# FMC_connector.net
KiCad netlist of a schematic drawn in Altium Designer
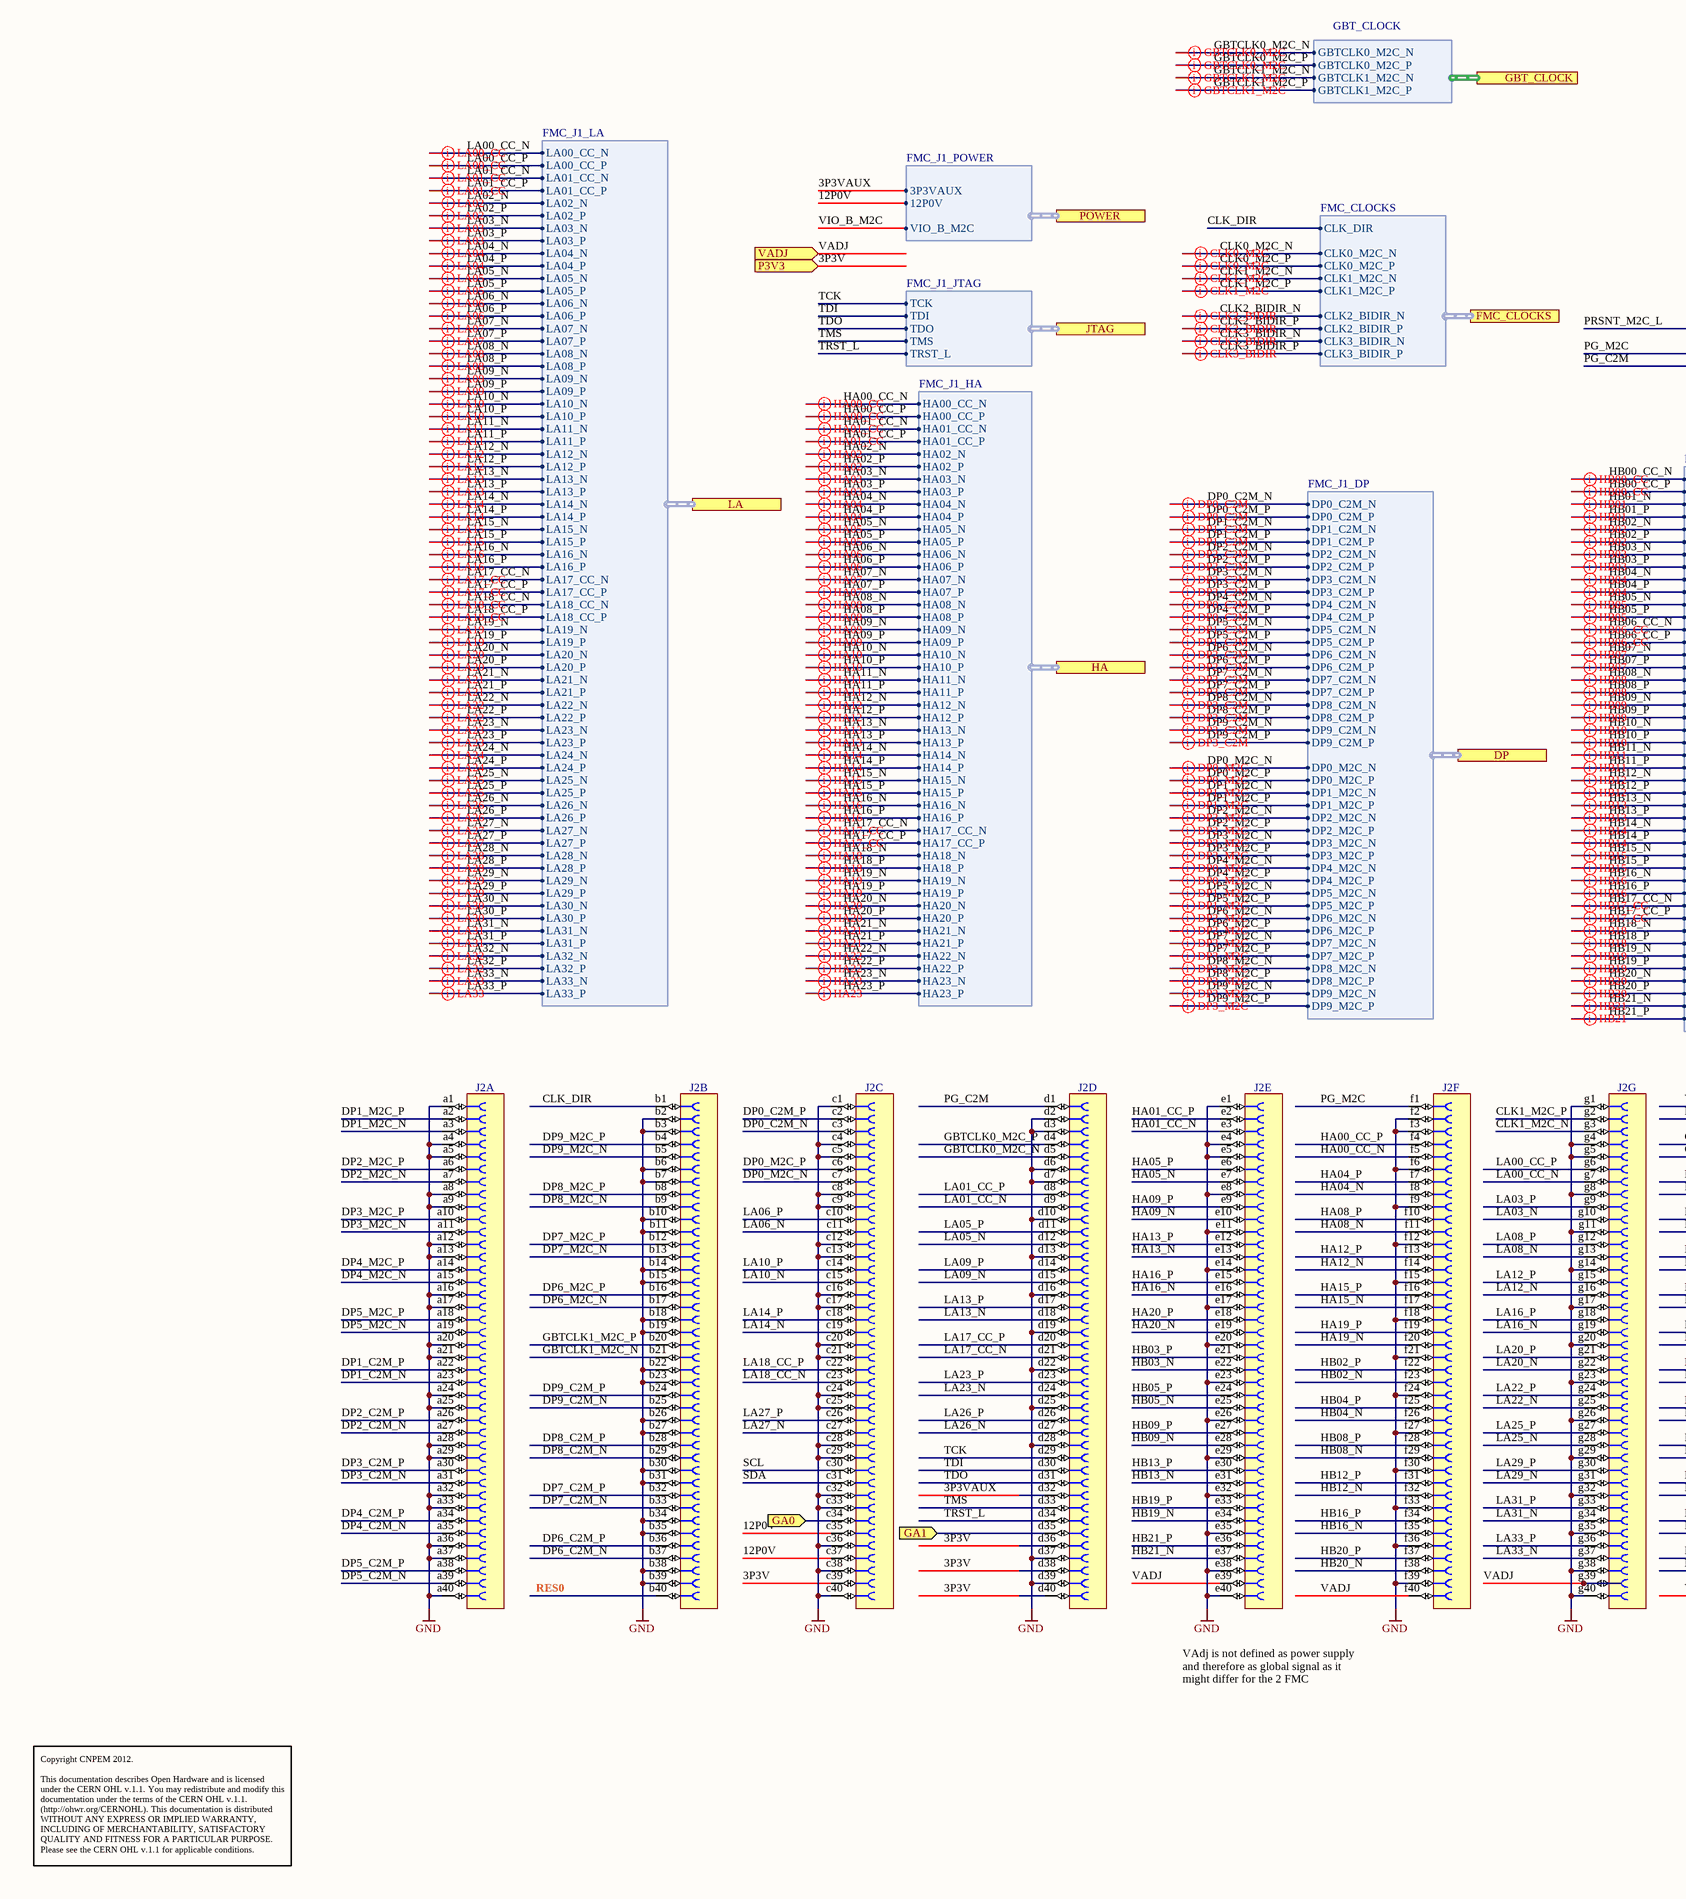
[diagram p0: FMC_connector.SchDoc, left]
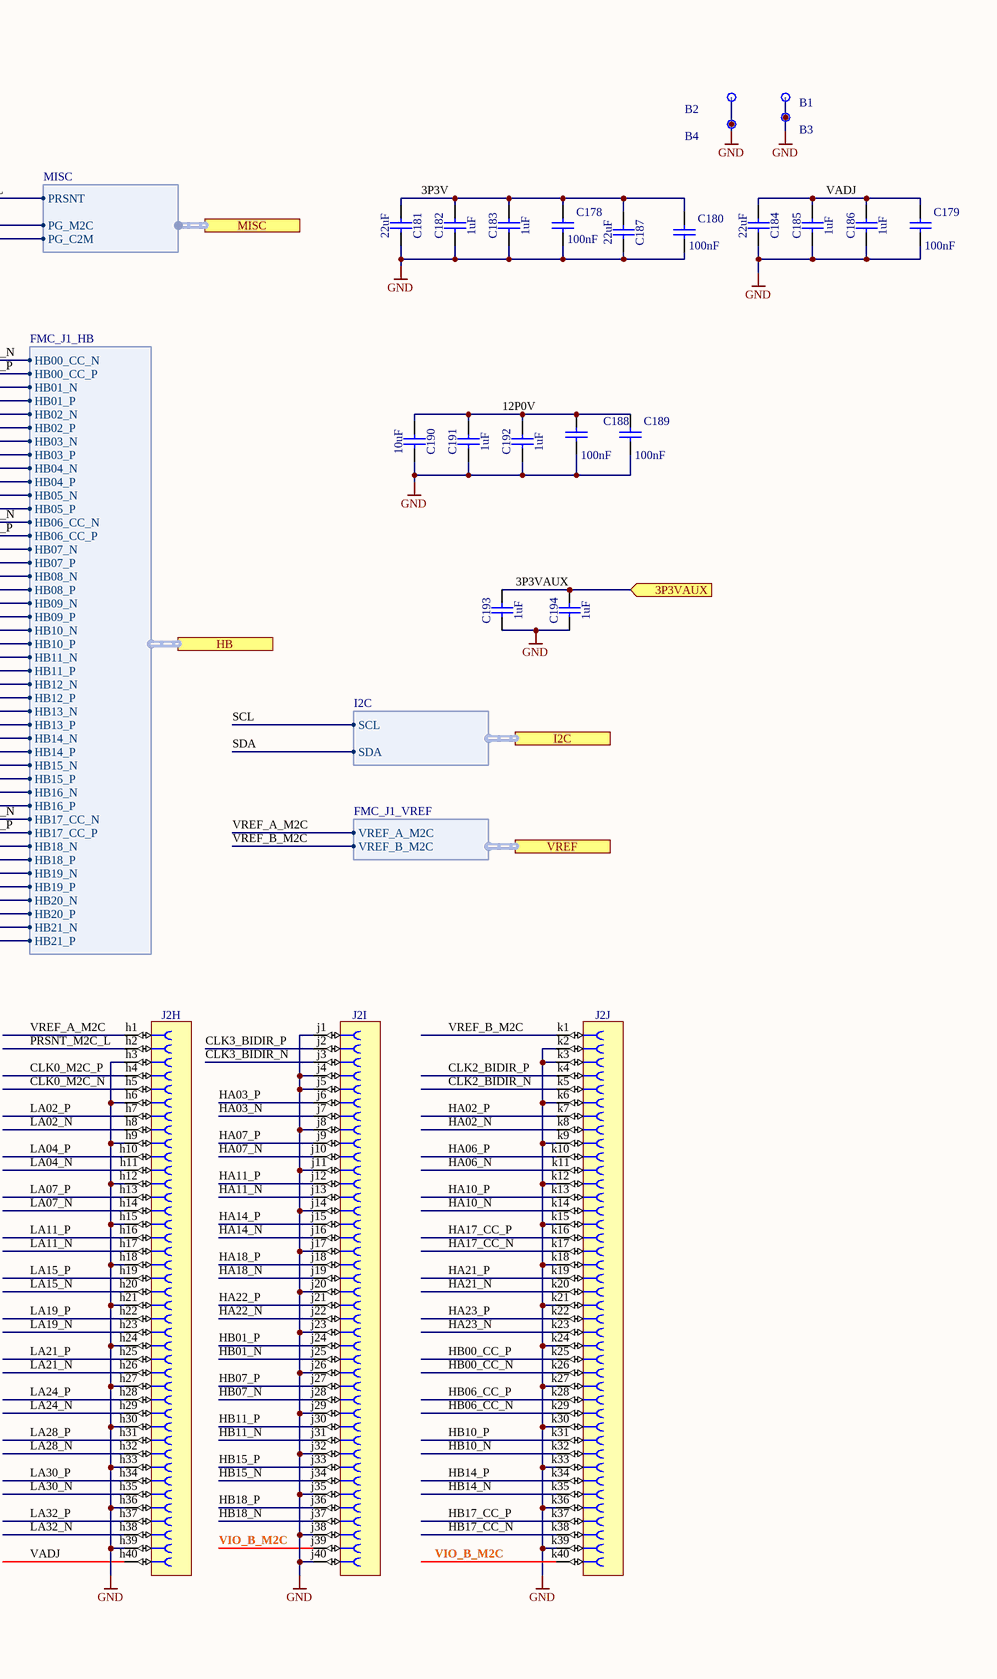
[diagram p1: FMC_connector.SchDoc, right]

(export (version "E")
  (design (tool "Eeschema 10.0.6"))
  (components
    (comp (ref "B1")
      (value "Plated Hole")
      (footprint "MTG270_500")
      (description "Single Terminal Socket")
      (fields (field (name "PART NUMBER") "PLATED_HOLE2.7_PAD5.0") (field (name "AUTHOR") "CERN DEM JMW"))
      (libsource (lib "Eletro-mechanical") (part "Single Terminal Socket"))
    )
    (comp (ref "B2")
      (value "Plated Hole")
      (footprint "MTG270_500")
      (description "Single Terminal Socket")
      (fields (field (name "PART NUMBER") "PLATED_HOLE2.7_PAD5.0") (field (name "AUTHOR") "CERN DEM JMW"))
      (libsource (lib "Eletro-mechanical") (part "Single Terminal Socket"))
    )
    (comp (ref "B3")
      (value "Plated Hole")
      (footprint "MTG270_500")
      (description "Single Terminal Socket")
      (fields (field (name "PART NUMBER") "PLATED_HOLE2.7_PAD5.0") (field (name "AUTHOR") "CERN DEM JMW"))
      (libsource (lib "Eletro-mechanical") (part "Single Terminal Socket"))
    )
    (comp (ref "B4")
      (value "Plated Hole")
      (footprint "MTG270_500")
      (description "Single Terminal Socket")
      (fields (field (name "PART NUMBER") "PLATED_HOLE2.7_PAD5.0") (field (name "AUTHOR") "CERN DEM JMW"))
      (libsource (lib "Eletro-mechanical") (part "Single Terminal Socket"))
    )
    (comp (ref "C178")
      (value "100nF")
      (footprint "CAPC0603X33N")
      (description "Non-polarised capacitor")
      (fields
        (field (name "PART NUMBER") "CC0201_100NF_6.3V_10%_X5R")
        (field (name "VOLTAGE") "6.3V")
        (field (name "AUTHOR") "CERN DEM JLC")
      )
      (libsource (lib "Capacitors") (part "Capacitor - non polarized"))
    )
    (comp (ref "C179")
      (value "100nF")
      (footprint "CAPC0603X33N")
      (description "Non-polarised capacitor")
      (fields
        (field (name "PART NUMBER") "CC0201_100NF_6.3V_10%_X5R")
        (field (name "VOLTAGE") "6.3V")
        (field (name "AUTHOR") "CERN DEM JLC")
      )
      (libsource (lib "Capacitors") (part "Capacitor - non polarized"))
    )
    (comp (ref "C180")
      (value "100nF")
      (footprint "CAPC0603X33N")
      (description "Non-polarised capacitor")
      (fields
        (field (name "PART NUMBER") "CC0201_100NF_6.3V_10%_X5R")
        (field (name "VOLTAGE") "6.3V")
        (field (name "AUTHOR") "CERN DEM JLC")
      )
      (libsource (lib "Capacitors") (part "Capacitor - non polarized"))
    )
    (comp (ref "C181")
      (value "22uF")
      (footprint "CAPC3216X180N")
      (description "Non-polarised capacitor")
      (fields
        (field (name "PART NUMBER") "CC1206_22UF_10V_10%_X7R")
        (field (name "VOLTAGE") "10V")
        (field (name "AUTHOR") "CERN DEM JLC")
      )
      (libsource (lib "Capacitors") (part "Capacitor - non polarized"))
    )
    (comp (ref "C182")
      (value "1uF")
      (footprint "CAPC1608X87N")
      (description "Non-polarised capacitor")
      (fields
        (field (name "PART NUMBER") "CC0603_1UF_25V_10%_X7R")
        (field (name "VOLTAGE") "25V")
        (field (name "AUTHOR") "CERN DEM JLC")
      )
      (libsource (lib "Capacitors") (part "Capacitor - non polarized"))
    )
    (comp (ref "C183")
      (value "1uF")
      (footprint "CAPC1608X87N")
      (description "Non-polarised capacitor")
      (fields
        (field (name "PART NUMBER") "CC0603_1UF_25V_10%_X7R")
        (field (name "VOLTAGE") "25V")
        (field (name "AUTHOR") "CERN DEM JLC")
      )
      (libsource (lib "Capacitors") (part "Capacitor - non polarized"))
    )
    (comp (ref "C184")
      (value "22uF")
      (footprint "CAPC3216X180N")
      (description "Non-polarised capacitor")
      (fields
        (field (name "PART NUMBER") "CC1206_22UF_10V_10%_X7R")
        (field (name "VOLTAGE") "10V")
        (field (name "AUTHOR") "CERN DEM JLC")
      )
      (libsource (lib "Capacitors") (part "Capacitor - non polarized"))
    )
    (comp (ref "C185")
      (value "1uF")
      (footprint "CAPC1608X87N")
      (description "Non-polarised capacitor")
      (fields
        (field (name "PART NUMBER") "CC0603_1UF_25V_10%_X7R")
        (field (name "VOLTAGE") "25V")
        (field (name "AUTHOR") "CERN DEM JLC")
      )
      (libsource (lib "Capacitors") (part "Capacitor - non polarized"))
    )
    (comp (ref "C186")
      (value "1uF")
      (footprint "CAPC1608X87N")
      (description "Non-polarised capacitor")
      (fields
        (field (name "PART NUMBER") "CC0603_1UF_25V_10%_X7R")
        (field (name "VOLTAGE") "25V")
        (field (name "AUTHOR") "CERN DEM JLC")
      )
      (libsource (lib "Capacitors") (part "Capacitor - non polarized"))
    )
    (comp (ref "C187")
      (value "22uF")
      (footprint "CAPC3216X180N")
      (description "Non-polarised capacitor")
      (fields
        (field (name "PART NUMBER") "CC1206_22UF_10V_10%_X7R")
        (field (name "VOLTAGE") "10V")
        (field (name "AUTHOR") "CERN DEM JLC")
      )
      (libsource (lib "Capacitors") (part "Capacitor - non polarized"))
    )
    (comp (ref "C188")
      (value "100nF")
      (footprint "CAPC0603X33N")
      (description "Non-polarised capacitor")
      (fields
        (field (name "PART NUMBER") "CC0201_100NF_6.3V_10%_X5R")
        (field (name "VOLTAGE") "6.3V")
        (field (name "AUTHOR") "CERN DEM JLC")
      )
      (libsource (lib "Capacitors") (part "Capacitor - non polarized"))
    )
    (comp (ref "C189")
      (value "100nF")
      (footprint "CAPC0603X33N")
      (description "Non-polarised capacitor")
      (fields
        (field (name "PART NUMBER") "CC0201_100NF_6.3V_10%_X5R")
        (field (name "VOLTAGE") "6.3V")
        (field (name "AUTHOR") "CERN DEM JLC")
      )
      (libsource (lib "Capacitors") (part "Capacitor - non polarized"))
    )
    (comp (ref "C190")
      (value "10uF")
      (footprint "CAPC2012X135N")
      (description "Non-polarised capacitor")
      (fields
        (field (name "PART NUMBER") "CC0805_10UF_16V_10%_X5R")
        (field (name "VOLTAGE") "16V")
        (field (name "AUTHOR") "CERN DEM JLC")
      )
      (libsource (lib "Capacitors") (part "Capacitor - non polarized"))
    )
    (comp (ref "C191")
      (value "1uF")
      (footprint "CAPC1608X87N")
      (description "Non-polarised capacitor")
      (fields
        (field (name "PART NUMBER") "CC0603_1UF_25V_10%_X7R")
        (field (name "VOLTAGE") "25V")
        (field (name "AUTHOR") "CERN DEM JLC")
      )
      (libsource (lib "Capacitors") (part "Capacitor - non polarized"))
    )
    (comp (ref "C192")
      (value "1uF")
      (footprint "CAPC1608X87N")
      (description "Non-polarised capacitor")
      (fields
        (field (name "PART NUMBER") "CC0603_1UF_25V_10%_X7R")
        (field (name "VOLTAGE") "25V")
        (field (name "AUTHOR") "CERN DEM JLC")
      )
      (libsource (lib "Capacitors") (part "Capacitor - non polarized"))
    )
    (comp (ref "C193")
      (value "1uF")
      (footprint "CAPC1608X87N")
      (description "Non-polarised capacitor")
      (fields
        (field (name "PART NUMBER") "CC0603_1UF_25V_10%_X7R")
        (field (name "VOLTAGE") "25V")
        (field (name "AUTHOR") "CERN DEM JLC")
      )
      (libsource (lib "Capacitors") (part "Capacitor - non polarized"))
    )
    (comp (ref "C194")
      (value "1uF")
      (footprint "CAPC1608X87N")
      (description "Non-polarised capacitor")
      (fields
        (field (name "PART NUMBER") "CC0603_1UF_25V_10%_X7R")
        (field (name "VOLTAGE") "25V")
        (field (name "AUTHOR") "CERN DEM JLC")
      )
      (libsource (lib "Capacitors") (part "Capacitor - non polarized"))
    )
    (comp (ref "J2")
      (value "VITA 57")
      (footprint "SAMTEC_ASP-134486-01")
      (description "Connector VITA 57, 400 Female contacts in 10 row abcdefghj")
      (fields
        (field (name "PART NUMBER") "SAMTEC_ASP-134486-01")
        (field (name "MANUFACTURER") "SAMTEC")
        (field (name "AUTHOR") "CERN DEM JLC")
      )
      (libsource (lib "Connectors") (part "Connector VITA 57 400 Female (abcdefghjk)"))
    )
  )
  (nets
    (net (code "12") (name "/3P3V") (class "Default")
      (node (ref "C178") (pin "2") (pinfunction "2_2") (pintype "passive"))
      (node (ref "C180") (pin "2") (pinfunction "2_2") (pintype "passive"))
      (node (ref "C181") (pin "1") (pinfunction "1_1") (pintype "passive"))
      (node (ref "C182") (pin "2") (pinfunction "2_2") (pintype "passive"))
      (node (ref "C183") (pin "2") (pinfunction "2_2") (pintype "passive"))
      (node (ref "C187") (pin "1") (pinfunction "1_1") (pintype "passive"))
      (node (ref "J2") (pin "c39") (pinfunction "c39_c39") (pintype "bidirectional"))
      (node (ref "J2") (pin "d36") (pinfunction "d36_d36") (pintype "bidirectional"))
      (node (ref "J2") (pin "d38") (pinfunction "d38_d38") (pintype "bidirectional"))
      (node (ref "J2") (pin "d40") (pinfunction "d40_d40") (pintype "bidirectional"))
    )
    (net (code "13") (name "/3P3VAUX") (class "Default")
      (node (ref "C193") (pin "2") (pinfunction "2_2") (pintype "passive"))
      (node (ref "C194") (pin "2") (pinfunction "2_2") (pintype "passive"))
      (node (ref "J2") (pin "d32") (pinfunction "d32_d32") (pintype "bidirectional"))
    )
    (net (code "14") (name "/12P0V") (class "Default")
      (node (ref "C188") (pin "2") (pinfunction "2_2") (pintype "passive"))
      (node (ref "C189") (pin "2") (pinfunction "2_2") (pintype "passive"))
      (node (ref "C190") (pin "1") (pinfunction "1_1") (pintype "passive"))
      (node (ref "C191") (pin "2") (pinfunction "2_2") (pintype "passive"))
      (node (ref "C192") (pin "2") (pinfunction "2_2") (pintype "passive"))
      (node (ref "J2") (pin "c35") (pinfunction "c35_c35") (pintype "bidirectional"))
      (node (ref "J2") (pin "c37") (pinfunction "c37_c37") (pintype "bidirectional"))
    )
    (net (code "15") (name "/CLK0_M2C_N") (class "Default")
      (node (ref "J2") (pin "h5") (pinfunction "h5_h5") (pintype "bidirectional"))
    )
    (net (code "16") (name "/CLK0_M2C_P") (class "Default")
      (node (ref "J2") (pin "h4") (pinfunction "h4_h4") (pintype "bidirectional"))
    )
    (net (code "17") (name "/CLK1_M2C_N") (class "Default")
      (node (ref "J2") (pin "g3") (pinfunction "g3_g3") (pintype "bidirectional"))
    )
    (net (code "18") (name "/CLK1_M2C_P") (class "Default")
      (node (ref "J2") (pin "g2") (pinfunction "g2_g2") (pintype "bidirectional"))
    )
    (net (code "19") (name "/CLK2_BIDIR_N") (class "Default")
      (node (ref "J2") (pin "k5") (pinfunction "k5_k5") (pintype "bidirectional"))
    )
    (net (code "20") (name "/CLK2_BIDIR_P") (class "Default")
      (node (ref "J2") (pin "k4") (pinfunction "k4_k4") (pintype "bidirectional"))
    )
    (net (code "21") (name "/CLK3_BIDIR_N") (class "Default")
      (node (ref "J2") (pin "j3") (pinfunction "j3_j3") (pintype "bidirectional"))
    )
    (net (code "22") (name "/CLK3_BIDIR_P") (class "Default")
      (node (ref "J2") (pin "j2") (pinfunction "j2_j2") (pintype "bidirectional"))
    )
    (net (code "23") (name "/CLK_DIR") (class "Default")
      (node (ref "J2") (pin "b1") (pinfunction "b1_b1") (pintype "bidirectional"))
    )
    (net (code "24") (name "/DP0_C2M_N") (class "Default")
      (node (ref "J2") (pin "c3") (pinfunction "c3_c3") (pintype "bidirectional"))
    )
    (net (code "25") (name "/DP0_C2M_P") (class "Default")
      (node (ref "J2") (pin "c2") (pinfunction "c2_c2") (pintype "bidirectional"))
    )
    (net (code "26") (name "/DP0_M2C_N") (class "Default")
      (node (ref "J2") (pin "c7") (pinfunction "c7_c7") (pintype "bidirectional"))
    )
    (net (code "27") (name "/DP0_M2C_P") (class "Default")
      (node (ref "J2") (pin "c6") (pinfunction "c6_c6") (pintype "bidirectional"))
    )
    (net (code "28") (name "/DP1_C2M_N") (class "Default")
      (node (ref "J2") (pin "a23") (pinfunction "a23_a23") (pintype "bidirectional"))
    )
    (net (code "29") (name "/DP1_C2M_P") (class "Default")
      (node (ref "J2") (pin "a22") (pinfunction "a22_a22") (pintype "bidirectional"))
    )
    (net (code "30") (name "/DP1_M2C_N") (class "Default")
      (node (ref "J2") (pin "a3") (pinfunction "a3_a3") (pintype "bidirectional"))
    )
    (net (code "31") (name "/DP1_M2C_P") (class "Default")
      (node (ref "J2") (pin "a2") (pinfunction "a2_a2") (pintype "bidirectional"))
    )
    (net (code "32") (name "/DP2_C2M_N") (class "Default")
      (node (ref "J2") (pin "a27") (pinfunction "a27_a27") (pintype "bidirectional"))
    )
    (net (code "33") (name "/DP2_C2M_P") (class "Default")
      (node (ref "J2") (pin "a26") (pinfunction "a26_a26") (pintype "bidirectional"))
    )
    (net (code "34") (name "/DP2_M2C_N") (class "Default")
      (node (ref "J2") (pin "a7") (pinfunction "a7_a7") (pintype "bidirectional"))
    )
    (net (code "35") (name "/DP2_M2C_P") (class "Default")
      (node (ref "J2") (pin "a6") (pinfunction "a6_a6") (pintype "bidirectional"))
    )
    (net (code "36") (name "/DP3_C2M_N") (class "Default")
      (node (ref "J2") (pin "a31") (pinfunction "a31_a31") (pintype "bidirectional"))
    )
    (net (code "37") (name "/DP3_C2M_P") (class "Default")
      (node (ref "J2") (pin "a30") (pinfunction "a30_a30") (pintype "bidirectional"))
    )
    (net (code "38") (name "/DP3_M2C_N") (class "Default")
      (node (ref "J2") (pin "a11") (pinfunction "a11_a11") (pintype "bidirectional"))
    )
    (net (code "39") (name "/DP3_M2C_P") (class "Default")
      (node (ref "J2") (pin "a10") (pinfunction "a10_a10") (pintype "bidirectional"))
    )
    (net (code "40") (name "/DP4_C2M_N") (class "Default")
      (node (ref "J2") (pin "a35") (pinfunction "a35_a35") (pintype "bidirectional"))
    )
    (net (code "41") (name "/DP4_C2M_P") (class "Default")
      (node (ref "J2") (pin "a34") (pinfunction "a34_a34") (pintype "bidirectional"))
    )
    (net (code "42") (name "/DP4_M2C_N") (class "Default")
      (node (ref "J2") (pin "a15") (pinfunction "a15_a15") (pintype "bidirectional"))
    )
    (net (code "43") (name "/DP4_M2C_P") (class "Default")
      (node (ref "J2") (pin "a14") (pinfunction "a14_a14") (pintype "bidirectional"))
    )
    (net (code "44") (name "/DP5_C2M_N") (class "Default")
      (node (ref "J2") (pin "a39") (pinfunction "a39_a39") (pintype "bidirectional"))
    )
    (net (code "45") (name "/DP5_C2M_P") (class "Default")
      (node (ref "J2") (pin "a38") (pinfunction "a38_a38") (pintype "bidirectional"))
    )
    (net (code "46") (name "/DP5_M2C_N") (class "Default")
      (node (ref "J2") (pin "a19") (pinfunction "a19_a19") (pintype "bidirectional"))
    )
    (net (code "47") (name "/DP5_M2C_P") (class "Default")
      (node (ref "J2") (pin "a18") (pinfunction "a18_a18") (pintype "bidirectional"))
    )
    (net (code "48") (name "/DP6_C2M_N") (class "Default")
      (node (ref "J2") (pin "b37") (pinfunction "b37_b37") (pintype "bidirectional"))
    )
    (net (code "49") (name "/DP6_C2M_P") (class "Default")
      (node (ref "J2") (pin "b36") (pinfunction "b36_b36") (pintype "bidirectional"))
    )
    (net (code "50") (name "/DP6_M2C_N") (class "Default")
      (node (ref "J2") (pin "b17") (pinfunction "b17_b17") (pintype "bidirectional"))
    )
    (net (code "51") (name "/DP6_M2C_P") (class "Default")
      (node (ref "J2") (pin "b16") (pinfunction "b16_b16") (pintype "bidirectional"))
    )
    (net (code "52") (name "/DP7_C2M_N") (class "Default")
      (node (ref "J2") (pin "b33") (pinfunction "b33_b33") (pintype "bidirectional"))
    )
    (net (code "53") (name "/DP7_C2M_P") (class "Default")
      (node (ref "J2") (pin "b32") (pinfunction "b32_b32") (pintype "bidirectional"))
    )
    (net (code "54") (name "/DP7_M2C_N") (class "Default")
      (node (ref "J2") (pin "b13") (pinfunction "b13_b13") (pintype "bidirectional"))
    )
    (net (code "55") (name "/DP7_M2C_P") (class "Default")
      (node (ref "J2") (pin "b12") (pinfunction "b12_b12") (pintype "bidirectional"))
    )
    (net (code "56") (name "/DP8_C2M_N") (class "Default")
      (node (ref "J2") (pin "b29") (pinfunction "b29_b29") (pintype "bidirectional"))
    )
    (net (code "57") (name "/DP8_C2M_P") (class "Default")
      (node (ref "J2") (pin "b28") (pinfunction "b28_b28") (pintype "bidirectional"))
    )
    (net (code "58") (name "/DP8_M2C_N") (class "Default")
      (node (ref "J2") (pin "b9") (pinfunction "b9_b9") (pintype "bidirectional"))
    )
    (net (code "59") (name "/DP8_M2C_P") (class "Default")
      (node (ref "J2") (pin "b8") (pinfunction "b8_b8") (pintype "bidirectional"))
    )
    (net (code "60") (name "/DP9_C2M_N") (class "Default")
      (node (ref "J2") (pin "b25") (pinfunction "b25_b25") (pintype "bidirectional"))
    )
    (net (code "61") (name "/DP9_C2M_P") (class "Default")
      (node (ref "J2") (pin "b24") (pinfunction "b24_b24") (pintype "bidirectional"))
    )
    (net (code "62") (name "/DP9_M2C_N") (class "Default")
      (node (ref "J2") (pin "b5") (pinfunction "b5_b5") (pintype "bidirectional"))
    )
    (net (code "63") (name "/DP9_M2C_P") (class "Default")
      (node (ref "J2") (pin "b4") (pinfunction "b4_b4") (pintype "bidirectional"))
    )
    (net (code "64") (name "/GA0") (class "Default")
      (node (ref "J2") (pin "c34") (pinfunction "c34_c34") (pintype "bidirectional"))
    )
    (net (code "65") (name "/GA1") (class "Default")
      (node (ref "J2") (pin "d35") (pinfunction "d35_d35") (pintype "bidirectional"))
    )
    (net (code "66") (name "/GBTCLK0_M2C_N") (class "Default")
      (node (ref "J2") (pin "d5") (pinfunction "d5_d5") (pintype "bidirectional"))
    )
    (net (code "67") (name "/GBTCLK0_M2C_P") (class "Default")
      (node (ref "J2") (pin "d4") (pinfunction "d4_d4") (pintype "bidirectional"))
    )
    (net (code "68") (name "/GBTCLK1_M2C_N") (class "Default")
      (node (ref "J2") (pin "b21") (pinfunction "b21_b21") (pintype "bidirectional"))
    )
    (net (code "69") (name "/GBTCLK1_M2C_P") (class "Default")
      (node (ref "J2") (pin "b20") (pinfunction "b20_b20") (pintype "bidirectional"))
    )
    (net (code "70") (name "/HA00_CC_N") (class "Default")
      (node (ref "J2") (pin "f5") (pinfunction "f5_f5") (pintype "bidirectional"))
    )
    (net (code "71") (name "/HA00_CC_P") (class "Default")
      (node (ref "J2") (pin "f4") (pinfunction "f4_f4") (pintype "bidirectional"))
    )
    (net (code "72") (name "/HA01_CC_N") (class "Default")
      (node (ref "J2") (pin "e3") (pinfunction "e3_e3") (pintype "bidirectional"))
    )
    (net (code "73") (name "/HA01_CC_P") (class "Default")
      (node (ref "J2") (pin "e2") (pinfunction "e2_e2") (pintype "bidirectional"))
    )
    (net (code "74") (name "/HA02_N") (class "Default")
      (node (ref "J2") (pin "k8") (pinfunction "k8_k8") (pintype "bidirectional"))
    )
    (net (code "75") (name "/HA02_P") (class "Default")
      (node (ref "J2") (pin "k7") (pinfunction "k7_k7") (pintype "bidirectional"))
    )
    (net (code "76") (name "/HA03_N") (class "Default")
      (node (ref "J2") (pin "j7") (pinfunction "j7_j7") (pintype "bidirectional"))
    )
    (net (code "77") (name "/HA03_P") (class "Default")
      (node (ref "J2") (pin "j6") (pinfunction "j6_j6") (pintype "bidirectional"))
    )
    (net (code "78") (name "/HA04_N") (class "Default")
      (node (ref "J2") (pin "f8") (pinfunction "f8_f8") (pintype "bidirectional"))
    )
    (net (code "79") (name "/HA04_P") (class "Default")
      (node (ref "J2") (pin "f7") (pinfunction "f7_f7") (pintype "bidirectional"))
    )
    (net (code "80") (name "/HA05_N") (class "Default")
      (node (ref "J2") (pin "e7") (pinfunction "e7_e7") (pintype "bidirectional"))
    )
    (net (code "81") (name "/HA05_P") (class "Default")
      (node (ref "J2") (pin "e6") (pinfunction "e6_e6") (pintype "bidirectional"))
    )
    (net (code "82") (name "/HA06_N") (class "Default")
      (node (ref "J2") (pin "k11") (pinfunction "k11_k11") (pintype "bidirectional"))
    )
    (net (code "83") (name "/HA06_P") (class "Default")
      (node (ref "J2") (pin "k10") (pinfunction "k10_k10") (pintype "bidirectional"))
    )
    (net (code "84") (name "/HA07_N") (class "Default")
      (node (ref "J2") (pin "j10") (pinfunction "j10_j10") (pintype "bidirectional"))
    )
    (net (code "85") (name "/HA07_P") (class "Default")
      (node (ref "J2") (pin "j9") (pinfunction "j9_j9") (pintype "bidirectional"))
    )
    (net (code "86") (name "/HA08_N") (class "Default")
      (node (ref "J2") (pin "f11") (pinfunction "f11_f11") (pintype "bidirectional"))
    )
    (net (code "87") (name "/HA08_P") (class "Default")
      (node (ref "J2") (pin "f10") (pinfunction "f10_f10") (pintype "bidirectional"))
    )
    (net (code "88") (name "/HA09_N") (class "Default")
      (node (ref "J2") (pin "e10") (pinfunction "e10_e10") (pintype "bidirectional"))
    )
    (net (code "89") (name "/HA09_P") (class "Default")
      (node (ref "J2") (pin "e9") (pinfunction "e9_e9") (pintype "bidirectional"))
    )
    (net (code "90") (name "/HA10_N") (class "Default")
      (node (ref "J2") (pin "k14") (pinfunction "k14_k14") (pintype "bidirectional"))
    )
    (net (code "91") (name "/HA10_P") (class "Default")
      (node (ref "J2") (pin "k13") (pinfunction "k13_k13") (pintype "bidirectional"))
    )
    (net (code "92") (name "/HA11_N") (class "Default")
      (node (ref "J2") (pin "j13") (pinfunction "j13_j13") (pintype "bidirectional"))
    )
    (net (code "93") (name "/HA11_P") (class "Default")
      (node (ref "J2") (pin "j12") (pinfunction "j12_j12") (pintype "bidirectional"))
    )
    (net (code "94") (name "/HA12_N") (class "Default")
      (node (ref "J2") (pin "f14") (pinfunction "f14_f14") (pintype "bidirectional"))
    )
    (net (code "95") (name "/HA12_P") (class "Default")
      (node (ref "J2") (pin "f13") (pinfunction "f13_f13") (pintype "bidirectional"))
    )
    (net (code "96") (name "/HA13_N") (class "Default")
      (node (ref "J2") (pin "e13") (pinfunction "e13_e13") (pintype "bidirectional"))
    )
    (net (code "97") (name "/HA13_P") (class "Default")
      (node (ref "J2") (pin "e12") (pinfunction "e12_e12") (pintype "bidirectional"))
    )
    (net (code "98") (name "/HA14_N") (class "Default")
      (node (ref "J2") (pin "j16") (pinfunction "j16_j16") (pintype "bidirectional"))
    )
    (net (code "99") (name "/HA14_P") (class "Default")
      (node (ref "J2") (pin "j15") (pinfunction "j15_j15") (pintype "bidirectional"))
    )
    (net (code "100") (name "/HA15_N") (class "Default")
      (node (ref "J2") (pin "f17") (pinfunction "f17_f17") (pintype "bidirectional"))
    )
    (net (code "101") (name "/HA15_P") (class "Default")
      (node (ref "J2") (pin "f16") (pinfunction "f16_f16") (pintype "bidirectional"))
    )
    (net (code "102") (name "/HA16_N") (class "Default")
      (node (ref "J2") (pin "e16") (pinfunction "e16_e16") (pintype "bidirectional"))
    )
    (net (code "103") (name "/HA16_P") (class "Default")
      (node (ref "J2") (pin "e15") (pinfunction "e15_e15") (pintype "bidirectional"))
    )
    (net (code "104") (name "/HA17_CC_N") (class "Default")
      (node (ref "J2") (pin "k17") (pinfunction "k17_k17") (pintype "bidirectional"))
    )
    (net (code "105") (name "/HA17_CC_P") (class "Default")
      (node (ref "J2") (pin "k16") (pinfunction "k16_k16") (pintype "bidirectional"))
    )
    (net (code "106") (name "/HA18_N") (class "Default")
      (node (ref "J2") (pin "j19") (pinfunction "j19_j19") (pintype "bidirectional"))
    )
    (net (code "107") (name "/HA18_P") (class "Default")
      (node (ref "J2") (pin "j18") (pinfunction "j18_j18") (pintype "bidirectional"))
    )
    (net (code "108") (name "/HA19_N") (class "Default")
      (node (ref "J2") (pin "f20") (pinfunction "f20_f20") (pintype "bidirectional"))
    )
    (net (code "109") (name "/HA19_P") (class "Default")
      (node (ref "J2") (pin "f19") (pinfunction "f19_f19") (pintype "bidirectional"))
    )
    (net (code "110") (name "/HA20_N") (class "Default")
      (node (ref "J2") (pin "e19") (pinfunction "e19_e19") (pintype "bidirectional"))
    )
    (net (code "111") (name "/HA20_P") (class "Default")
      (node (ref "J2") (pin "e18") (pinfunction "e18_e18") (pintype "bidirectional"))
    )
    (net (code "112") (name "/HA21_N") (class "Default")
      (node (ref "J2") (pin "k20") (pinfunction "k20_k20") (pintype "bidirectional"))
    )
    (net (code "113") (name "/HA21_P") (class "Default")
      (node (ref "J2") (pin "k19") (pinfunction "k19_k19") (pintype "bidirectional"))
    )
    (net (code "114") (name "/HA22_N") (class "Default")
      (node (ref "J2") (pin "j22") (pinfunction "j22_j22") (pintype "bidirectional"))
    )
    (net (code "115") (name "/HA22_P") (class "Default")
      (node (ref "J2") (pin "j21") (pinfunction "j21_j21") (pintype "bidirectional"))
    )
    (net (code "116") (name "/HA23_N") (class "Default")
      (node (ref "J2") (pin "k23") (pinfunction "k23_k23") (pintype "bidirectional"))
    )
    (net (code "117") (name "/HA23_P") (class "Default")
      (node (ref "J2") (pin "k22") (pinfunction "k22_k22") (pintype "bidirectional"))
    )
    (net (code "118") (name "/HB00_CC_N") (class "Default")
      (node (ref "J2") (pin "k26") (pinfunction "k26_k26") (pintype "bidirectional"))
    )
    (net (code "119") (name "/HB00_CC_P") (class "Default")
      (node (ref "J2") (pin "k25") (pinfunction "k25_k25") (pintype "bidirectional"))
    )
    (net (code "120") (name "/HB01_N") (class "Default")
      (node (ref "J2") (pin "j25") (pinfunction "j25_j25") (pintype "bidirectional"))
    )
    (net (code "121") (name "/HB01_P") (class "Default")
      (node (ref "J2") (pin "j24") (pinfunction "j24_j24") (pintype "bidirectional"))
    )
    (net (code "122") (name "/HB02_N") (class "Default")
      (node (ref "J2") (pin "f23") (pinfunction "f23_f23") (pintype "bidirectional"))
    )
    (net (code "123") (name "/HB02_P") (class "Default")
      (node (ref "J2") (pin "f22") (pinfunction "f22_f22") (pintype "bidirectional"))
    )
    (net (code "124") (name "/HB03_N") (class "Default")
      (node (ref "J2") (pin "e22") (pinfunction "e22_e22") (pintype "bidirectional"))
    )
    (net (code "125") (name "/HB03_P") (class "Default")
      (node (ref "J2") (pin "e21") (pinfunction "e21_e21") (pintype "bidirectional"))
    )
    (net (code "126") (name "/HB04_N") (class "Default")
      (node (ref "J2") (pin "f26") (pinfunction "f26_f26") (pintype "bidirectional"))
    )
    (net (code "127") (name "/HB04_P") (class "Default")
      (node (ref "J2") (pin "f25") (pinfunction "f25_f25") (pintype "bidirectional"))
    )
    (net (code "128") (name "/HB05_N") (class "Default")
      (node (ref "J2") (pin "e25") (pinfunction "e25_e25") (pintype "bidirectional"))
    )
    (net (code "129") (name "/HB05_P") (class "Default")
      (node (ref "J2") (pin "e24") (pinfunction "e24_e24") (pintype "bidirectional"))
    )
    (net (code "130") (name "/HB06_CC_N") (class "Default")
      (node (ref "J2") (pin "k29") (pinfunction "k29_k29") (pintype "bidirectional"))
    )
    (net (code "131") (name "/HB06_CC_P") (class "Default")
      (node (ref "J2") (pin "k28") (pinfunction "k28_k28") (pintype "bidirectional"))
    )
    (net (code "132") (name "/HB07_N") (class "Default")
      (node (ref "J2") (pin "j28") (pinfunction "j28_j28") (pintype "bidirectional"))
    )
    (net (code "133") (name "/HB07_P") (class "Default")
      (node (ref "J2") (pin "j27") (pinfunction "j27_j27") (pintype "bidirectional"))
    )
    (net (code "134") (name "/HB08_N") (class "Default")
      (node (ref "J2") (pin "f29") (pinfunction "f29_f29") (pintype "bidirectional"))
    )
    (net (code "135") (name "/HB08_P") (class "Default")
      (node (ref "J2") (pin "f28") (pinfunction "f28_f28") (pintype "bidirectional"))
    )
    (net (code "136") (name "/HB09_N") (class "Default")
      (node (ref "J2") (pin "e28") (pinfunction "e28_e28") (pintype "bidirectional"))
    )
    (net (code "137") (name "/HB09_P") (class "Default")
      (node (ref "J2") (pin "e27") (pinfunction "e27_e27") (pintype "bidirectional"))
    )
    (net (code "138") (name "/HB10_N") (class "Default")
      (node (ref "J2") (pin "k32") (pinfunction "k32_k32") (pintype "bidirectional"))
    )
    (net (code "139") (name "/HB10_P") (class "Default")
      (node (ref "J2") (pin "k31") (pinfunction "k31_k31") (pintype "bidirectional"))
    )
    (net (code "140") (name "/HB11_N") (class "Default")
      (node (ref "J2") (pin "j31") (pinfunction "j31_j31") (pintype "bidirectional"))
    )
    (net (code "141") (name "/HB11_P") (class "Default")
      (node (ref "J2") (pin "j30") (pinfunction "j30_j30") (pintype "bidirectional"))
    )
    (net (code "142") (name "/HB12_N") (class "Default")
      (node (ref "J2") (pin "f32") (pinfunction "f32_f32") (pintype "bidirectional"))
    )
    (net (code "143") (name "/HB12_P") (class "Default")
      (node (ref "J2") (pin "f31") (pinfunction "f31_f31") (pintype "bidirectional"))
    )
    (net (code "144") (name "/HB13_N") (class "Default")
      (node (ref "J2") (pin "e31") (pinfunction "e31_e31") (pintype "bidirectional"))
    )
    (net (code "145") (name "/HB13_P") (class "Default")
      (node (ref "J2") (pin "e30") (pinfunction "e30_e30") (pintype "bidirectional"))
    )
    (net (code "146") (name "/HB14_N") (class "Default")
      (node (ref "J2") (pin "k35") (pinfunction "k35_k35") (pintype "bidirectional"))
    )
    (net (code "147") (name "/HB14_P") (class "Default")
      (node (ref "J2") (pin "k34") (pinfunction "k34_k34") (pintype "bidirectional"))
    )
    (net (code "148") (name "/HB15_N") (class "Default")
      (node (ref "J2") (pin "j34") (pinfunction "j34_j34") (pintype "bidirectional"))
    )
    (net (code "149") (name "/HB15_P") (class "Default")
      (node (ref "J2") (pin "j33") (pinfunction "j33_j33") (pintype "bidirectional"))
    )
    (net (code "150") (name "/HB16_N") (class "Default")
      (node (ref "J2") (pin "f35") (pinfunction "f35_f35") (pintype "bidirectional"))
    )
    (net (code "151") (name "/HB16_P") (class "Default")
      (node (ref "J2") (pin "f34") (pinfunction "f34_f34") (pintype "bidirectional"))
    )
    (net (code "152") (name "/HB17_CC_N") (class "Default")
      (node (ref "J2") (pin "k38") (pinfunction "k38_k38") (pintype "bidirectional"))
    )
    (net (code "153") (name "/HB17_CC_P") (class "Default")
      (node (ref "J2") (pin "k37") (pinfunction "k37_k37") (pintype "bidirectional"))
    )
    (net (code "154") (name "/HB18_N") (class "Default")
      (node (ref "J2") (pin "j37") (pinfunction "j37_j37") (pintype "bidirectional"))
    )
    (net (code "155") (name "/HB18_P") (class "Default")
      (node (ref "J2") (pin "j36") (pinfunction "j36_j36") (pintype "bidirectional"))
    )
    (net (code "156") (name "/HB19_N") (class "Default")
      (node (ref "J2") (pin "e34") (pinfunction "e34_e34") (pintype "bidirectional"))
    )
    (net (code "157") (name "/HB19_P") (class "Default")
      (node (ref "J2") (pin "e33") (pinfunction "e33_e33") (pintype "bidirectional"))
    )
    (net (code "158") (name "/HB20_N") (class "Default")
      (node (ref "J2") (pin "f38") (pinfunction "f38_f38") (pintype "bidirectional"))
    )
    (net (code "159") (name "/HB20_P") (class "Default")
      (node (ref "J2") (pin "f37") (pinfunction "f37_f37") (pintype "bidirectional"))
    )
    (net (code "160") (name "/HB21_N") (class "Default")
      (node (ref "J2") (pin "e37") (pinfunction "e37_e37") (pintype "bidirectional"))
    )
    (net (code "161") (name "/HB21_P") (class "Default")
      (node (ref "J2") (pin "e36") (pinfunction "e36_e36") (pintype "bidirectional"))
    )
    (net (code "162") (name "/LA00_CC_N") (class "Default")
      (node (ref "J2") (pin "g7") (pinfunction "g7_g7") (pintype "bidirectional"))
    )
    (net (code "163") (name "/LA00_CC_P") (class "Default")
      (node (ref "J2") (pin "g6") (pinfunction "g6_g6") (pintype "bidirectional"))
    )
    (net (code "164") (name "/LA01_CC_N") (class "Default")
      (node (ref "J2") (pin "d9") (pinfunction "d9_d9") (pintype "bidirectional"))
    )
    (net (code "165") (name "/LA01_CC_P") (class "Default")
      (node (ref "J2") (pin "d8") (pinfunction "d8_d8") (pintype "bidirectional"))
    )
    (net (code "166") (name "/LA02_N") (class "Default")
      (node (ref "J2") (pin "h8") (pinfunction "h8_h8") (pintype "bidirectional"))
    )
    (net (code "167") (name "/LA02_P") (class "Default")
      (node (ref "J2") (pin "h7") (pinfunction "h7_h7") (pintype "bidirectional"))
    )
    (net (code "168") (name "/LA03_N") (class "Default")
      (node (ref "J2") (pin "g10") (pinfunction "g10_g10") (pintype "bidirectional"))
    )
    (net (code "169") (name "/LA03_P") (class "Default")
      (node (ref "J2") (pin "g9") (pinfunction "g9_g9") (pintype "bidirectional"))
    )
    (net (code "170") (name "/LA04_N") (class "Default")
      (node (ref "J2") (pin "h11") (pinfunction "h11_h11") (pintype "bidirectional"))
    )
    (net (code "171") (name "/LA04_P") (class "Default")
      (node (ref "J2") (pin "h10") (pinfunction "h10_h10") (pintype "bidirectional"))
    )
    (net (code "172") (name "/LA05_N") (class "Default")
      (node (ref "J2") (pin "d12") (pinfunction "d12_d12") (pintype "bidirectional"))
    )
    (net (code "173") (name "/LA05_P") (class "Default")
      (node (ref "J2") (pin "d11") (pinfunction "d11_d11") (pintype "bidirectional"))
    )
    (net (code "174") (name "/LA06_N") (class "Default")
      (node (ref "J2") (pin "c11") (pinfunction "c11_c11") (pintype "bidirectional"))
    )
    (net (code "175") (name "/LA06_P") (class "Default")
      (node (ref "J2") (pin "c10") (pinfunction "c10_c10") (pintype "bidirectional"))
    )
    (net (code "176") (name "/LA07_N") (class "Default")
      (node (ref "J2") (pin "h14") (pinfunction "h14_h14") (pintype "bidirectional"))
    )
    (net (code "177") (name "/LA07_P") (class "Default")
      (node (ref "J2") (pin "h13") (pinfunction "h13_h13") (pintype "bidirectional"))
    )
    (net (code "178") (name "/LA08_N") (class "Default")
      (node (ref "J2") (pin "g13") (pinfunction "g13_g13") (pintype "bidirectional"))
    )
    (net (code "179") (name "/LA08_P") (class "Default")
      (node (ref "J2") (pin "g12") (pinfunction "g12_g12") (pintype "bidirectional"))
    )
    (net (code "180") (name "/LA09_N") (class "Default")
      (node (ref "J2") (pin "d15") (pinfunction "d15_d15") (pintype "bidirectional"))
    )
    (net (code "181") (name "/LA09_P") (class "Default")
      (node (ref "J2") (pin "d14") (pinfunction "d14_d14") (pintype "bidirectional"))
    )
    (net (code "182") (name "/LA10_N") (class "Default")
      (node (ref "J2") (pin "c15") (pinfunction "c15_c15") (pintype "bidirectional"))
    )
    (net (code "183") (name "/LA10_P") (class "Default")
      (node (ref "J2") (pin "c14") (pinfunction "c14_c14") (pintype "bidirectional"))
    )
    (net (code "184") (name "/LA11_N") (class "Default")
      (node (ref "J2") (pin "h17") (pinfunction "h17_h17") (pintype "bidirectional"))
    )
    (net (code "185") (name "/LA11_P") (class "Default")
      (node (ref "J2") (pin "h16") (pinfunction "h16_h16") (pintype "bidirectional"))
    )
    (net (code "186") (name "/LA12_N") (class "Default")
      (node (ref "J2") (pin "g16") (pinfunction "g16_g16") (pintype "bidirectional"))
    )
    (net (code "187") (name "/LA12_P") (class "Default")
      (node (ref "J2") (pin "g15") (pinfunction "g15_g15") (pintype "bidirectional"))
    )
    (net (code "188") (name "/LA13_N") (class "Default")
      (node (ref "J2") (pin "d18") (pinfunction "d18_d18") (pintype "bidirectional"))
    )
    (net (code "189") (name "/LA13_P") (class "Default")
      (node (ref "J2") (pin "d17") (pinfunction "d17_d17") (pintype "bidirectional"))
    )
    (net (code "190") (name "/LA14_N") (class "Default")
      (node (ref "J2") (pin "c19") (pinfunction "c19_c19") (pintype "bidirectional"))
    )
    (net (code "191") (name "/LA14_P") (class "Default")
      (node (ref "J2") (pin "c18") (pinfunction "c18_c18") (pintype "bidirectional"))
    )
    (net (code "192") (name "/LA15_N") (class "Default")
      (node (ref "J2") (pin "h20") (pinfunction "h20_h20") (pintype "bidirectional"))
    )
    (net (code "193") (name "/LA15_P") (class "Default")
      (node (ref "J2") (pin "h19") (pinfunction "h19_h19") (pintype "bidirectional"))
    )
    (net (code "194") (name "/LA16_N") (class "Default")
      (node (ref "J2") (pin "g19") (pinfunction "g19_g19") (pintype "bidirectional"))
    )
    (net (code "195") (name "/LA16_P") (class "Default")
      (node (ref "J2") (pin "g18") (pinfunction "g18_g18") (pintype "bidirectional"))
    )
    (net (code "196") (name "/LA17_CC_N") (class "Default")
      (node (ref "J2") (pin "d21") (pinfunction "d21_d21") (pintype "bidirectional"))
    )
    (net (code "197") (name "/LA17_CC_P") (class "Default")
      (node (ref "J2") (pin "d20") (pinfunction "d20_d20") (pintype "bidirectional"))
    )
    (net (code "198") (name "/LA18_CC_N") (class "Default")
      (node (ref "J2") (pin "c23") (pinfunction "c23_c23") (pintype "bidirectional"))
    )
    (net (code "199") (name "/LA18_CC_P") (class "Default")
      (node (ref "J2") (pin "c22") (pinfunction "c22_c22") (pintype "bidirectional"))
    )
    (net (code "200") (name "/LA19_N") (class "Default")
      (node (ref "J2") (pin "h23") (pinfunction "h23_h23") (pintype "bidirectional"))
    )
    (net (code "201") (name "/LA19_P") (class "Default")
      (node (ref "J2") (pin "h22") (pinfunction "h22_h22") (pintype "bidirectional"))
    )
    (net (code "202") (name "/LA20_N") (class "Default")
      (node (ref "J2") (pin "g22") (pinfunction "g22_g22") (pintype "bidirectional"))
    )
    (net (code "203") (name "/LA20_P") (class "Default")
      (node (ref "J2") (pin "g21") (pinfunction "g21_g21") (pintype "bidirectional"))
    )
    (net (code "204") (name "/LA21_N") (class "Default")
      (node (ref "J2") (pin "h26") (pinfunction "h26_h26") (pintype "bidirectional"))
    )
    (net (code "205") (name "/LA21_P") (class "Default")
      (node (ref "J2") (pin "h25") (pinfunction "h25_h25") (pintype "bidirectional"))
    )
    (net (code "206") (name "/LA22_N") (class "Default")
      (node (ref "J2") (pin "g25") (pinfunction "g25_g25") (pintype "bidirectional"))
    )
    (net (code "207") (name "/LA22_P") (class "Default")
      (node (ref "J2") (pin "g24") (pinfunction "g24_g24") (pintype "bidirectional"))
    )
    (net (code "208") (name "/LA23_N") (class "Default")
      (node (ref "J2") (pin "d24") (pinfunction "d24_d24") (pintype "bidirectional"))
    )
    (net (code "209") (name "/LA23_P") (class "Default")
      (node (ref "J2") (pin "d23") (pinfunction "d23_d23") (pintype "bidirectional"))
    )
    (net (code "210") (name "/LA24_N") (class "Default")
      (node (ref "J2") (pin "h29") (pinfunction "h29_h29") (pintype "bidirectional"))
    )
    (net (code "211") (name "/LA24_P") (class "Default")
      (node (ref "J2") (pin "h28") (pinfunction "h28_h28") (pintype "bidirectional"))
    )
    (net (code "212") (name "/LA25_N") (class "Default")
      (node (ref "J2") (pin "g28") (pinfunction "g28_g28") (pintype "bidirectional"))
    )
    (net (code "213") (name "/LA25_P") (class "Default")
      (node (ref "J2") (pin "g27") (pinfunction "g27_g27") (pintype "bidirectional"))
    )
    (net (code "214") (name "/LA26_N") (class "Default")
      (node (ref "J2") (pin "d27") (pinfunction "d27_d27") (pintype "bidirectional"))
    )
    (net (code "215") (name "/LA26_P") (class "Default")
      (node (ref "J2") (pin "d26") (pinfunction "d26_d26") (pintype "bidirectional"))
    )
    (net (code "216") (name "/LA27_N") (class "Default")
      (node (ref "J2") (pin "c27") (pinfunction "c27_c27") (pintype "bidirectional"))
    )
    (net (code "217") (name "/LA27_P") (class "Default")
      (node (ref "J2") (pin "c26") (pinfunction "c26_c26") (pintype "bidirectional"))
    )
    (net (code "218") (name "/LA28_N") (class "Default")
      (node (ref "J2") (pin "h32") (pinfunction "h32_h32") (pintype "bidirectional"))
    )
    (net (code "219") (name "/LA28_P") (class "Default")
      (node (ref "J2") (pin "h31") (pinfunction "h31_h31") (pintype "bidirectional"))
    )
    (net (code "220") (name "/LA29_N") (class "Default")
      (node (ref "J2") (pin "g31") (pinfunction "g31_g31") (pintype "bidirectional"))
    )
    (net (code "221") (name "/LA29_P") (class "Default")
      (node (ref "J2") (pin "g30") (pinfunction "g30_g30") (pintype "bidirectional"))
    )
    (net (code "222") (name "/LA30_N") (class "Default")
      (node (ref "J2") (pin "h35") (pinfunction "h35_h35") (pintype "bidirectional"))
    )
    (net (code "223") (name "/LA30_P") (class "Default")
      (node (ref "J2") (pin "h34") (pinfunction "h34_h34") (pintype "bidirectional"))
    )
    (net (code "224") (name "/LA31_N") (class "Default")
      (node (ref "J2") (pin "g34") (pinfunction "g34_g34") (pintype "bidirectional"))
    )
    (net (code "225") (name "/LA31_P") (class "Default")
      (node (ref "J2") (pin "g33") (pinfunction "g33_g33") (pintype "bidirectional"))
    )
    (net (code "226") (name "/LA32_N") (class "Default")
      (node (ref "J2") (pin "h38") (pinfunction "h38_h38") (pintype "bidirectional"))
    )
    (net (code "227") (name "/LA32_P") (class "Default")
      (node (ref "J2") (pin "h37") (pinfunction "h37_h37") (pintype "bidirectional"))
    )
    (net (code "228") (name "/LA33_N") (class "Default")
      (node (ref "J2") (pin "g37") (pinfunction "g37_g37") (pintype "bidirectional"))
    )
    (net (code "229") (name "/LA33_P") (class "Default")
      (node (ref "J2") (pin "g36") (pinfunction "g36_g36") (pintype "bidirectional"))
    )
    (net (code "230") (name "/PG_C2M") (class "Default")
      (node (ref "J2") (pin "d1") (pinfunction "d1_d1") (pintype "bidirectional"))
    )
    (net (code "231") (name "/PG_M2C") (class "Default")
      (node (ref "J2") (pin "f1") (pinfunction "f1_f1") (pintype "bidirectional"))
    )
    (net (code "232") (name "/PRSNT_M2C_L") (class "Default")
      (node (ref "J2") (pin "h2") (pinfunction "h2_h2") (pintype "bidirectional"))
    )
    (net (code "233") (name "/SCL") (class "Default")
      (node (ref "J2") (pin "c30") (pinfunction "c30_c30") (pintype "bidirectional"))
    )
    (net (code "234") (name "/SDA") (class "Default")
      (node (ref "J2") (pin "c31") (pinfunction "c31_c31") (pintype "bidirectional"))
    )
    (net (code "235") (name "/TCK") (class "Default")
      (node (ref "J2") (pin "d29") (pinfunction "d29_d29") (pintype "bidirectional"))
    )
    (net (code "236") (name "/TDI") (class "Default")
      (node (ref "J2") (pin "d30") (pinfunction "d30_d30") (pintype "bidirectional"))
    )
    (net (code "237") (name "/TDO") (class "Default")
      (node (ref "J2") (pin "d31") (pinfunction "d31_d31") (pintype "bidirectional"))
    )
    (net (code "238") (name "/TMS") (class "Default")
      (node (ref "J2") (pin "d33") (pinfunction "d33_d33") (pintype "bidirectional"))
    )
    (net (code "239") (name "/TRST_L") (class "Default")
      (node (ref "J2") (pin "d34") (pinfunction "d34_d34") (pintype "bidirectional"))
    )
    (net (code "240") (name "/VADJ") (class "Default")
      (node (ref "C179") (pin "2") (pinfunction "2_2") (pintype "passive"))
      (node (ref "C184") (pin "1") (pinfunction "1_1") (pintype "passive"))
      (node (ref "C185") (pin "2") (pinfunction "2_2") (pintype "passive"))
      (node (ref "C186") (pin "2") (pinfunction "2_2") (pintype "passive"))
      (node (ref "J2") (pin "e39") (pinfunction "e39_e39") (pintype "bidirectional"))
      (node (ref "J2") (pin "f40") (pinfunction "f40_f40") (pintype "bidirectional"))
      (node (ref "J2") (pin "g39") (pinfunction "g39_g39") (pintype "bidirectional"))
      (node (ref "J2") (pin "h40") (pinfunction "h40_h40") (pintype "bidirectional"))
    )
    (net (code "242") (name "/VREF_A_M2C") (class "Default")
      (node (ref "J2") (pin "h1") (pinfunction "h1_h1") (pintype "bidirectional"))
    )
    (net (code "243") (name "/VREF_B_M2C") (class "Default")
      (node (ref "J2") (pin "k1") (pinfunction "k1_k1") (pintype "bidirectional"))
    )
    (net (code "255") (name "GND") (class "Default")
      (node (ref "B1") (pin "1") (pinfunction "1_1") (pintype "bidirectional"))
      (node (ref "B2") (pin "1") (pinfunction "1_1") (pintype "bidirectional"))
      (node (ref "B3") (pin "1") (pinfunction "1_1") (pintype "bidirectional"))
      (node (ref "B4") (pin "1") (pinfunction "1_1") (pintype "bidirectional"))
      (node (ref "C178") (pin "1") (pinfunction "1_1") (pintype "passive"))
      (node (ref "C179") (pin "1") (pinfunction "1_1") (pintype "passive"))
      (node (ref "C180") (pin "1") (pinfunction "1_1") (pintype "passive"))
      (node (ref "C181") (pin "2") (pinfunction "2_2") (pintype "passive"))
      (node (ref "C182") (pin "1") (pinfunction "1_1") (pintype "passive"))
      (node (ref "C183") (pin "1") (pinfunction "1_1") (pintype "passive"))
      (node (ref "C184") (pin "2") (pinfunction "2_2") (pintype "passive"))
      (node (ref "C185") (pin "1") (pinfunction "1_1") (pintype "passive"))
      (node (ref "C186") (pin "1") (pinfunction "1_1") (pintype "passive"))
      (node (ref "C187") (pin "2") (pinfunction "2_2") (pintype "passive"))
      (node (ref "C188") (pin "1") (pinfunction "1_1") (pintype "passive"))
      (node (ref "C189") (pin "1") (pinfunction "1_1") (pintype "passive"))
      (node (ref "C190") (pin "2") (pinfunction "2_2") (pintype "passive"))
      (node (ref "C191") (pin "1") (pinfunction "1_1") (pintype "passive"))
      (node (ref "C192") (pin "1") (pinfunction "1_1") (pintype "passive"))
      (node (ref "C193") (pin "1") (pinfunction "1_1") (pintype "passive"))
      (node (ref "C194") (pin "1") (pinfunction "1_1") (pintype "passive"))
      (node (ref "J2") (pin "a1") (pinfunction "a1_a1") (pintype "bidirectional"))
      (node (ref "J2") (pin "a12") (pinfunction "a12_a12") (pintype "bidirectional"))
      (node (ref "J2") (pin "a13") (pinfunction "a13_a13") (pintype "bidirectional"))
      (node (ref "J2") (pin "a16") (pinfunction "a16_a16") (pintype "bidirectional"))
      (node (ref "J2") (pin "a17") (pinfunction "a17_a17") (pintype "bidirectional"))
      (node (ref "J2") (pin "a20") (pinfunction "a20_a20") (pintype "bidirectional"))
      (node (ref "J2") (pin "a21") (pinfunction "a21_a21") (pintype "bidirectional"))
      (node (ref "J2") (pin "a24") (pinfunction "a24_a24") (pintype "bidirectional"))
      (node (ref "J2") (pin "a25") (pinfunction "a25_a25") (pintype "bidirectional"))
      (node (ref "J2") (pin "a28") (pinfunction "a28_a28") (pintype "bidirectional"))
      (node (ref "J2") (pin "a29") (pinfunction "a29_a29") (pintype "bidirectional"))
      (node (ref "J2") (pin "a32") (pinfunction "a32_a32") (pintype "bidirectional"))
      (node (ref "J2") (pin "a33") (pinfunction "a33_a33") (pintype "bidirectional"))
      (node (ref "J2") (pin "a36") (pinfunction "a36_a36") (pintype "bidirectional"))
      (node (ref "J2") (pin "a37") (pinfunction "a37_a37") (pintype "bidirectional"))
      (node (ref "J2") (pin "a4") (pinfunction "a4_a4") (pintype "bidirectional"))
      (node (ref "J2") (pin "a40") (pinfunction "a40_a40") (pintype "bidirectional"))
      (node (ref "J2") (pin "a5") (pinfunction "a5_a5") (pintype "bidirectional"))
      (node (ref "J2") (pin "a8") (pinfunction "a8_a8") (pintype "bidirectional"))
      (node (ref "J2") (pin "a9") (pinfunction "a9_a9") (pintype "bidirectional"))
      (node (ref "J2") (pin "b10") (pinfunction "b10_b10") (pintype "bidirectional"))
      (node (ref "J2") (pin "b11") (pinfunction "b11_b11") (pintype "bidirectional"))
      (node (ref "J2") (pin "b14") (pinfunction "b14_b14") (pintype "bidirectional"))
      (node (ref "J2") (pin "b15") (pinfunction "b15_b15") (pintype "bidirectional"))
      (node (ref "J2") (pin "b18") (pinfunction "b18_b18") (pintype "bidirectional"))
      (node (ref "J2") (pin "b19") (pinfunction "b19_b19") (pintype "bidirectional"))
      (node (ref "J2") (pin "b2") (pinfunction "b2_b2") (pintype "bidirectional"))
      (node (ref "J2") (pin "b22") (pinfunction "b22_b22") (pintype "bidirectional"))
      (node (ref "J2") (pin "b23") (pinfunction "b23_b23") (pintype "bidirectional"))
      (node (ref "J2") (pin "b26") (pinfunction "b26_b26") (pintype "bidirectional"))
      (node (ref "J2") (pin "b27") (pinfunction "b27_b27") (pintype "bidirectional"))
      (node (ref "J2") (pin "b3") (pinfunction "b3_b3") (pintype "bidirectional"))
      (node (ref "J2") (pin "b30") (pinfunction "b30_b30") (pintype "bidirectional"))
      (node (ref "J2") (pin "b31") (pinfunction "b31_b31") (pintype "bidirectional"))
      (node (ref "J2") (pin "b34") (pinfunction "b34_b34") (pintype "bidirectional"))
      (node (ref "J2") (pin "b35") (pinfunction "b35_b35") (pintype "bidirectional"))
      (node (ref "J2") (pin "b38") (pinfunction "b38_b38") (pintype "bidirectional"))
      (node (ref "J2") (pin "b39") (pinfunction "b39_b39") (pintype "bidirectional"))
      (node (ref "J2") (pin "b6") (pinfunction "b6_b6") (pintype "bidirectional"))
      (node (ref "J2") (pin "b7") (pinfunction "b7_b7") (pintype "bidirectional"))
      (node (ref "J2") (pin "c1") (pinfunction "c1_c1") (pintype "bidirectional"))
      (node (ref "J2") (pin "c12") (pinfunction "c12_c12") (pintype "bidirectional"))
      (node (ref "J2") (pin "c13") (pinfunction "c13_c13") (pintype "bidirectional"))
      (node (ref "J2") (pin "c16") (pinfunction "c16_c16") (pintype "bidirectional"))
      (node (ref "J2") (pin "c17") (pinfunction "c17_c17") (pintype "bidirectional"))
      (node (ref "J2") (pin "c20") (pinfunction "c20_c20") (pintype "bidirectional"))
      (node (ref "J2") (pin "c21") (pinfunction "c21_c21") (pintype "bidirectional"))
      (node (ref "J2") (pin "c24") (pinfunction "c24_c24") (pintype "bidirectional"))
      (node (ref "J2") (pin "c25") (pinfunction "c25_c25") (pintype "bidirectional"))
      (node (ref "J2") (pin "c28") (pinfunction "c28_c28") (pintype "bidirectional"))
      (node (ref "J2") (pin "c29") (pinfunction "c29_c29") (pintype "bidirectional"))
      (node (ref "J2") (pin "c32") (pinfunction "c32_c32") (pintype "bidirectional"))
      (node (ref "J2") (pin "c33") (pinfunction "c33_c33") (pintype "bidirectional"))
      (node (ref "J2") (pin "c36") (pinfunction "c36_c36") (pintype "bidirectional"))
      (node (ref "J2") (pin "c38") (pinfunction "c38_c38") (pintype "bidirectional"))
      (node (ref "J2") (pin "c4") (pinfunction "c4_c4") (pintype "bidirectional"))
      (node (ref "J2") (pin "c40") (pinfunction "c40_c40") (pintype "bidirectional"))
      (node (ref "J2") (pin "c5") (pinfunction "c5_c5") (pintype "bidirectional"))
      (node (ref "J2") (pin "c8") (pinfunction "c8_c8") (pintype "bidirectional"))
      (node (ref "J2") (pin "c9") (pinfunction "c9_c9") (pintype "bidirectional"))
      (node (ref "J2") (pin "d10") (pinfunction "d10_d10") (pintype "bidirectional"))
      (node (ref "J2") (pin "d13") (pinfunction "d13_d13") (pintype "bidirectional"))
      (node (ref "J2") (pin "d16") (pinfunction "d16_d16") (pintype "bidirectional"))
      (node (ref "J2") (pin "d19") (pinfunction "d19_d19") (pintype "bidirectional"))
      (node (ref "J2") (pin "d2") (pinfunction "d2_d2") (pintype "bidirectional"))
      (node (ref "J2") (pin "d22") (pinfunction "d22_d22") (pintype "bidirectional"))
      (node (ref "J2") (pin "d25") (pinfunction "d25_d25") (pintype "bidirectional"))
      (node (ref "J2") (pin "d28") (pinfunction "d28_d28") (pintype "bidirectional"))
      (node (ref "J2") (pin "d3") (pinfunction "d3_d3") (pintype "bidirectional"))
      (node (ref "J2") (pin "d37") (pinfunction "d37_d37") (pintype "bidirectional"))
      (node (ref "J2") (pin "d39") (pinfunction "d39_d39") (pintype "bidirectional"))
      (node (ref "J2") (pin "d6") (pinfunction "d6_d6") (pintype "bidirectional"))
      (node (ref "J2") (pin "d7") (pinfunction "d7_d7") (pintype "bidirectional"))
      (node (ref "J2") (pin "e1") (pinfunction "e1_e1") (pintype "bidirectional"))
      (node (ref "J2") (pin "e11") (pinfunction "e11_e11") (pintype "bidirectional"))
      (node (ref "J2") (pin "e14") (pinfunction "e14_e14") (pintype "bidirectional"))
      (node (ref "J2") (pin "e17") (pinfunction "e17_e17") (pintype "bidirectional"))
      (node (ref "J2") (pin "e20") (pinfunction "e20_e20") (pintype "bidirectional"))
      (node (ref "J2") (pin "e23") (pinfunction "e23_e23") (pintype "bidirectional"))
      (node (ref "J2") (pin "e26") (pinfunction "e26_e26") (pintype "bidirectional"))
      (node (ref "J2") (pin "e29") (pinfunction "e29_e29") (pintype "bidirectional"))
      (node (ref "J2") (pin "e32") (pinfunction "e32_e32") (pintype "bidirectional"))
      (node (ref "J2") (pin "e35") (pinfunction "e35_e35") (pintype "bidirectional"))
      (node (ref "J2") (pin "e38") (pinfunction "e38_e38") (pintype "bidirectional"))
      (node (ref "J2") (pin "e4") (pinfunction "e4_e4") (pintype "bidirectional"))
      (node (ref "J2") (pin "e40") (pinfunction "e40_e40") (pintype "bidirectional"))
      (node (ref "J2") (pin "e5") (pinfunction "e5_e5") (pintype "bidirectional"))
      (node (ref "J2") (pin "e8") (pinfunction "e8_e8") (pintype "bidirectional"))
      (node (ref "J2") (pin "f12") (pinfunction "f12_f12") (pintype "bidirectional"))
      (node (ref "J2") (pin "f15") (pinfunction "f15_f15") (pintype "bidirectional"))
      (node (ref "J2") (pin "f18") (pinfunction "f18_f18") (pintype "bidirectional"))
      (node (ref "J2") (pin "f2") (pinfunction "f2_f2") (pintype "bidirectional"))
      (node (ref "J2") (pin "f21") (pinfunction "f21_f21") (pintype "bidirectional"))
      (node (ref "J2") (pin "f24") (pinfunction "f24_f24") (pintype "bidirectional"))
      (node (ref "J2") (pin "f27") (pinfunction "f27_f27") (pintype "bidirectional"))
      (node (ref "J2") (pin "f3") (pinfunction "f3_f3") (pintype "bidirectional"))
      (node (ref "J2") (pin "f30") (pinfunction "f30_f30") (pintype "bidirectional"))
      (node (ref "J2") (pin "f33") (pinfunction "f33_f33") (pintype "bidirectional"))
      (node (ref "J2") (pin "f36") (pinfunction "f36_f36") (pintype "bidirectional"))
      (node (ref "J2") (pin "f39") (pinfunction "f39_f39") (pintype "bidirectional"))
      (node (ref "J2") (pin "f6") (pinfunction "f6_f6") (pintype "bidirectional"))
      (node (ref "J2") (pin "f9") (pinfunction "f9_f9") (pintype "bidirectional"))
      (node (ref "J2") (pin "g1") (pinfunction "g1_g1") (pintype "bidirectional"))
      (node (ref "J2") (pin "g11") (pinfunction "g11_g11") (pintype "bidirectional"))
      (node (ref "J2") (pin "g14") (pinfunction "g14_g14") (pintype "bidirectional"))
      (node (ref "J2") (pin "g17") (pinfunction "g17_g17") (pintype "bidirectional"))
      (node (ref "J2") (pin "g20") (pinfunction "g20_g20") (pintype "bidirectional"))
      (node (ref "J2") (pin "g23") (pinfunction "g23_g23") (pintype "bidirectional"))
      (node (ref "J2") (pin "g26") (pinfunction "g26_g26") (pintype "bidirectional"))
      (node (ref "J2") (pin "g29") (pinfunction "g29_g29") (pintype "bidirectional"))
      (node (ref "J2") (pin "g32") (pinfunction "g32_g32") (pintype "bidirectional"))
      (node (ref "J2") (pin "g35") (pinfunction "g35_g35") (pintype "bidirectional"))
      (node (ref "J2") (pin "g38") (pinfunction "g38_g38") (pintype "bidirectional"))
      (node (ref "J2") (pin "g4") (pinfunction "g4_g4") (pintype "bidirectional"))
      (node (ref "J2") (pin "g40") (pinfunction "g40_g40") (pintype "bidirectional"))
      (node (ref "J2") (pin "g5") (pinfunction "g5_g5") (pintype "bidirectional"))
      (node (ref "J2") (pin "g8") (pinfunction "g8_g8") (pintype "bidirectional"))
      (node (ref "J2") (pin "h12") (pinfunction "h12_h12") (pintype "bidirectional"))
      (node (ref "J2") (pin "h15") (pinfunction "h15_h15") (pintype "bidirectional"))
      (node (ref "J2") (pin "h18") (pinfunction "h18_h18") (pintype "bidirectional"))
      (node (ref "J2") (pin "h21") (pinfunction "h21_h21") (pintype "bidirectional"))
      (node (ref "J2") (pin "h24") (pinfunction "h24_h24") (pintype "bidirectional"))
      (node (ref "J2") (pin "h27") (pinfunction "h27_h27") (pintype "bidirectional"))
      (node (ref "J2") (pin "h3") (pinfunction "h3_h3") (pintype "bidirectional"))
      (node (ref "J2") (pin "h30") (pinfunction "h30_h30") (pintype "bidirectional"))
      (node (ref "J2") (pin "h33") (pinfunction "h33_h33") (pintype "bidirectional"))
      (node (ref "J2") (pin "h36") (pinfunction "h36_h36") (pintype "bidirectional"))
      (node (ref "J2") (pin "h39") (pinfunction "h39_h39") (pintype "bidirectional"))
      (node (ref "J2") (pin "h6") (pinfunction "h6_h6") (pintype "bidirectional"))
      (node (ref "J2") (pin "h9") (pinfunction "h9_h9") (pintype "bidirectional"))
      (node (ref "J2") (pin "j1") (pinfunction "j1_j1") (pintype "bidirectional"))
      (node (ref "J2") (pin "j11") (pinfunction "j11_j11") (pintype "bidirectional"))
      (node (ref "J2") (pin "j14") (pinfunction "j14_j14") (pintype "bidirectional"))
      (node (ref "J2") (pin "j17") (pinfunction "j17_j17") (pintype "bidirectional"))
      (node (ref "J2") (pin "j20") (pinfunction "j20_j20") (pintype "bidirectional"))
      (node (ref "J2") (pin "j23") (pinfunction "j23_j23") (pintype "bidirectional"))
      (node (ref "J2") (pin "j26") (pinfunction "j26_j26") (pintype "bidirectional"))
      (node (ref "J2") (pin "j29") (pinfunction "j29_j29") (pintype "bidirectional"))
      (node (ref "J2") (pin "j32") (pinfunction "j32_j32") (pintype "bidirectional"))
      (node (ref "J2") (pin "j35") (pinfunction "j35_j35") (pintype "bidirectional"))
      (node (ref "J2") (pin "j38") (pinfunction "j38_j38") (pintype "bidirectional"))
      (node (ref "J2") (pin "j4") (pinfunction "j4_j4") (pintype "bidirectional"))
      (node (ref "J2") (pin "j40") (pinfunction "j40_j40") (pintype "bidirectional"))
      (node (ref "J2") (pin "j5") (pinfunction "j5_j5") (pintype "bidirectional"))
      (node (ref "J2") (pin "j8") (pinfunction "j8_j8") (pintype "bidirectional"))
      (node (ref "J2") (pin "k12") (pinfunction "k12_k12") (pintype "bidirectional"))
      (node (ref "J2") (pin "k15") (pinfunction "k15_k15") (pintype "bidirectional"))
      (node (ref "J2") (pin "k18") (pinfunction "k18_k18") (pintype "bidirectional"))
      (node (ref "J2") (pin "k2") (pinfunction "k2_k2") (pintype "bidirectional"))
      (node (ref "J2") (pin "k21") (pinfunction "k21_k21") (pintype "bidirectional"))
      (node (ref "J2") (pin "k24") (pinfunction "k24_k24") (pintype "bidirectional"))
      (node (ref "J2") (pin "k27") (pinfunction "k27_k27") (pintype "bidirectional"))
      (node (ref "J2") (pin "k3") (pinfunction "k3_k3") (pintype "bidirectional"))
      (node (ref "J2") (pin "k30") (pinfunction "k30_k30") (pintype "bidirectional"))
      (node (ref "J2") (pin "k33") (pinfunction "k33_k33") (pintype "bidirectional"))
      (node (ref "J2") (pin "k36") (pinfunction "k36_k36") (pintype "bidirectional"))
      (node (ref "J2") (pin "k39") (pinfunction "k39_k39") (pintype "bidirectional"))
      (node (ref "J2") (pin "k6") (pinfunction "k6_k6") (pintype "bidirectional"))
      (node (ref "J2") (pin "k9") (pinfunction "k9_k9") (pintype "bidirectional"))
    )
    (net (code "256") (name "unconnected-(J2-Padb40)") (class "Default")
      (node (ref "J2") (pin "b40") (pinfunction "b40_b40") (pintype "bidirectional"))
    )
    (net (code "257") (name "unconnected-(J2-Padj39)") (class "Default")
      (node (ref "J2") (pin "j39") (pinfunction "j39_j39") (pintype "bidirectional"))
    )
    (net (code "258") (name "unconnected-(J2-Padk40)") (class "Default")
      (node (ref "J2") (pin "k40") (pinfunction "k40_k40") (pintype "bidirectional"))
    )
  )
)
